# Sh3_Power.net
KiCad netlist of a schematic drawn in Altium Designer
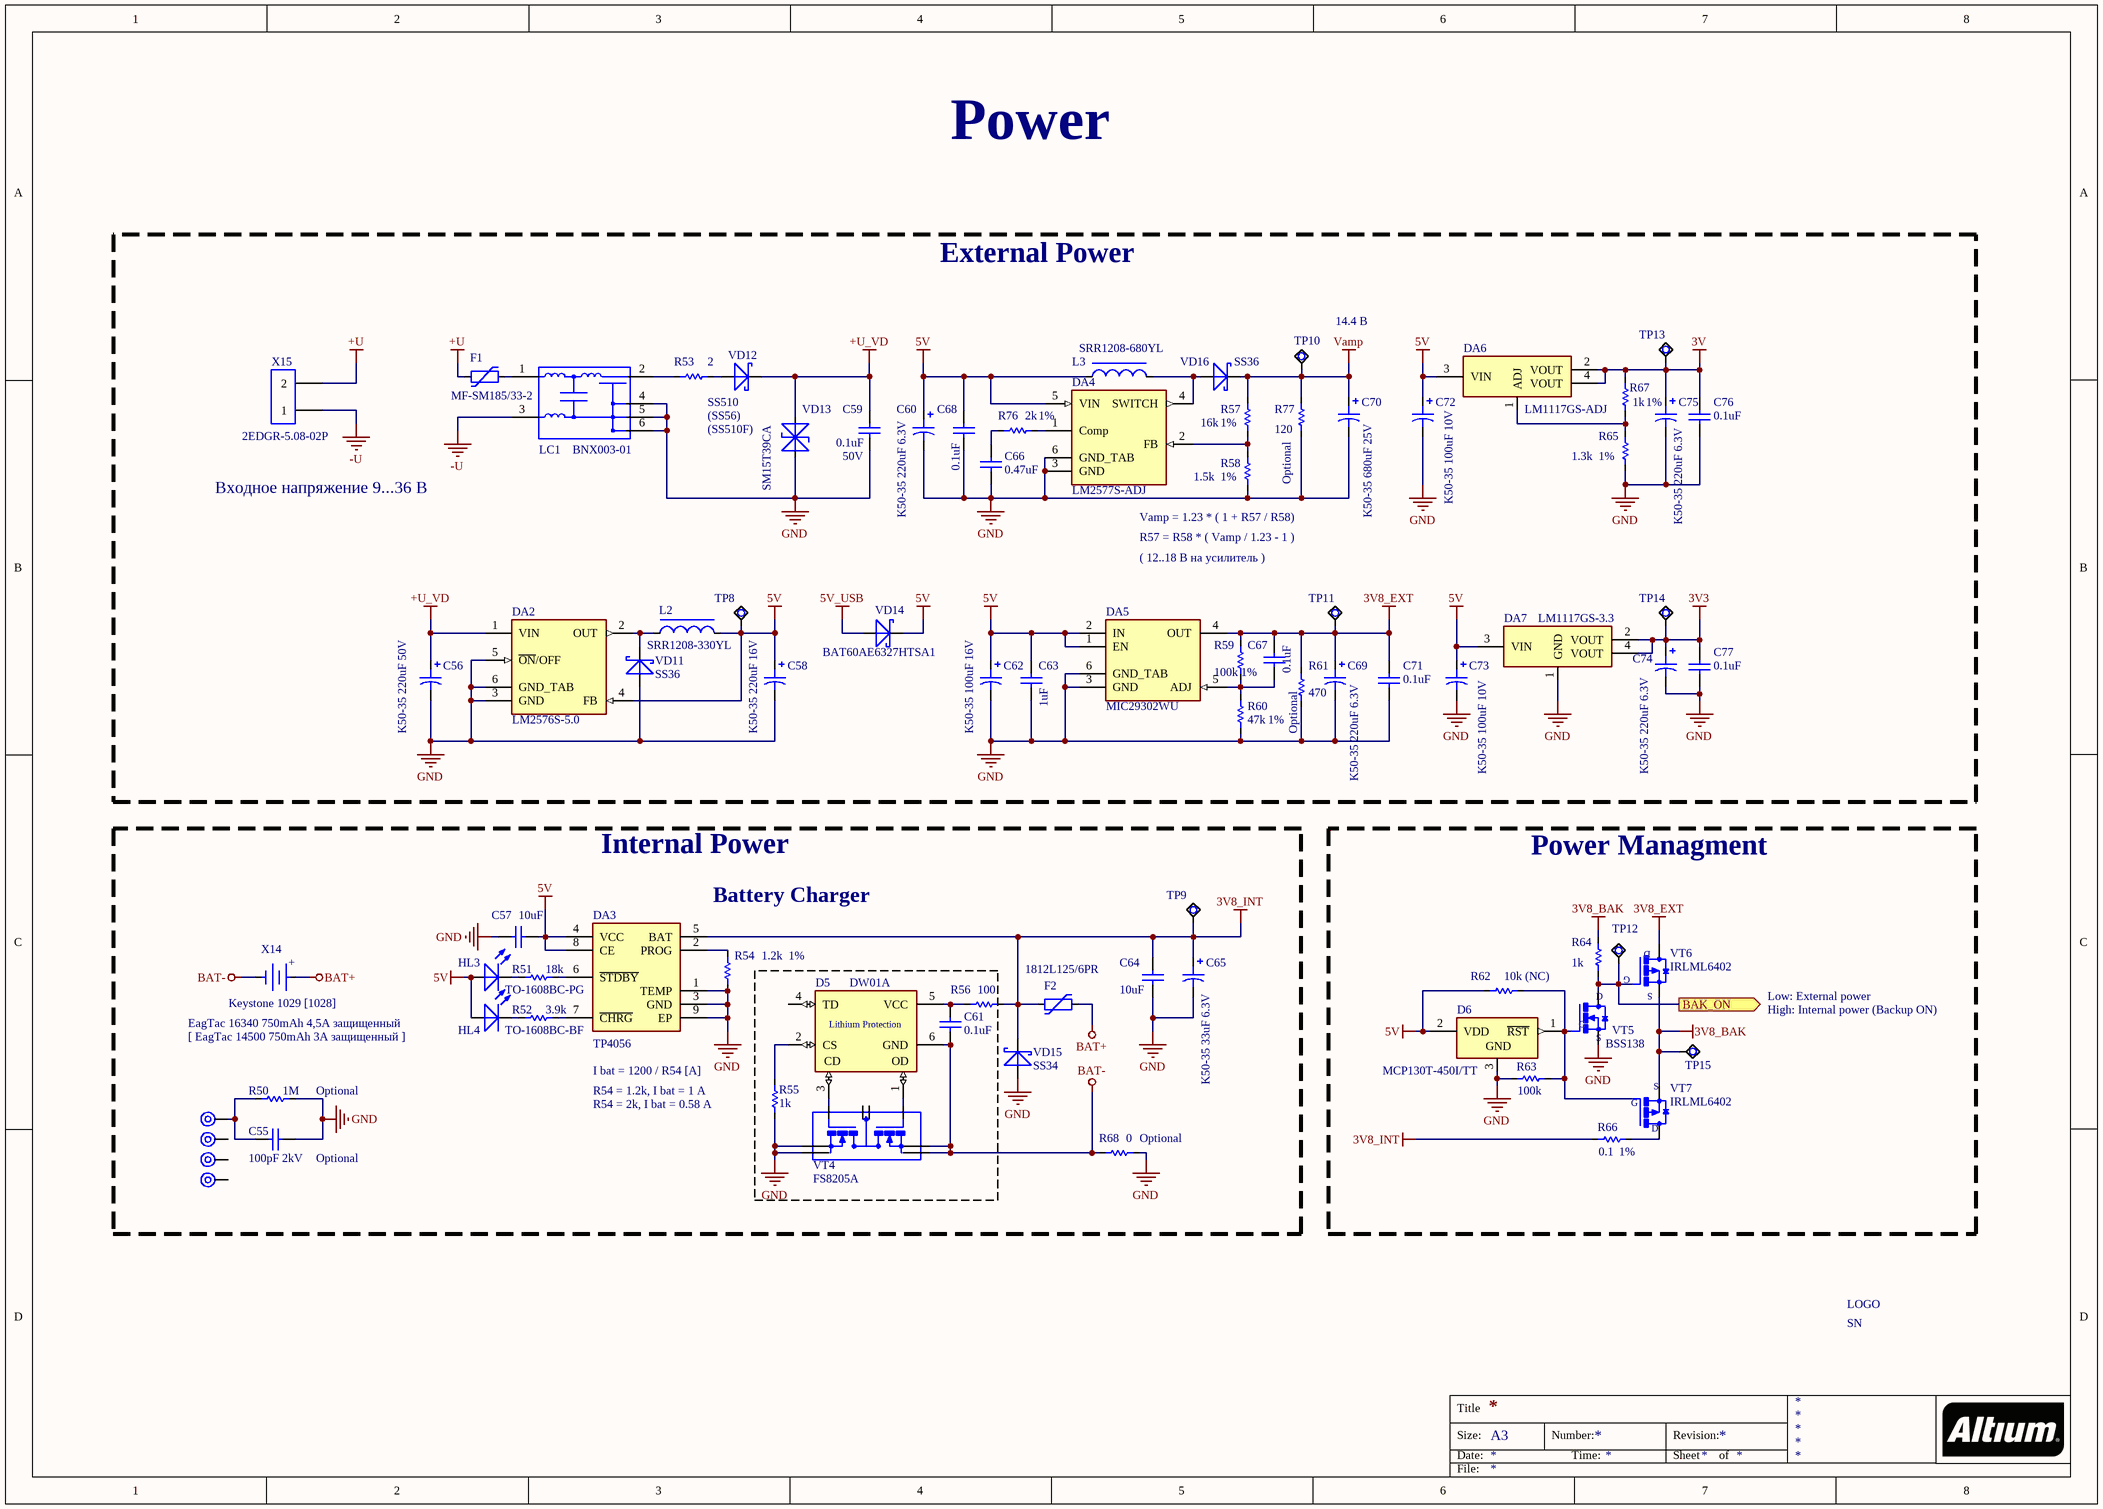
[diagram p0: Sh3_Power.SchDoc]

(export (version "E")
  (design (tool "Eeschema 10.0.6"))
  (components
    (comp (ref "BC1")
      (value "Mounting Hole")
      (footprint "body_connection_1")
      (libsource (lib "MyCompLib") (part "BodyConnector"))
    )
    (comp (ref "BC2")
      (value "Mounting Hole")
      (footprint "body_connection_1")
      (libsource (lib "MyCompLib") (part "BodyConnector"))
    )
    (comp (ref "BC3")
      (value "Mounting Hole")
      (footprint "body_connection_1")
      (libsource (lib "MyCompLib") (part "BodyConnector"))
    )
    (comp (ref "BC4")
      (value "Mounting Hole")
      (footprint "body_connection_1")
      (libsource (lib "MyCompLib") (part "BodyConnector"))
    )
    (comp (ref "C55")
      (value "100pF 2kV")
      (footprint "C_SMD1206")
      (description "C1206C101KGRACAUTO (CC1206JKNPODBN101)")
      (libsource (lib "MyCompLib") (part "C_SMD"))
    )
    (comp (ref "C56")
      (value "K50-35 220uF 50V")
      (footprint "K50-35 10x12.5x5")
      (description "SH050M0220B5S-1012 ECAP 10*12\r\nКонденсатор электролитический алюминиевый")
      (libsource (lib "MyCompLib") (part "K50-35"))
    )
    (comp (ref "C57")
      (value "10uF")
      (footprint "C_SMD0603")
      (description "GRM188R61E106M")
      (libsource (lib "MyCompLib") (part "C_SMD"))
    )
    (comp (ref "C58")
      (value "K50-35 220uF 16V")
      (footprint "K50-35 6.3x11x2.5")
      (description "ECA1CM221 6.3x11 P:2,5мм Конденсатор электролитический алюминиевый")
      (libsource (lib "MyCompLib") (part "K50-35"))
    )
    (comp (ref "C59")
      (value "0.1uF")
      (footprint "C_SMD0603")
      (description "GRM188R71H104KA93D")
      (libsource (lib "MyCompLib") (part "C_SMD"))
    )
    (comp (ref "C60")
      (value "K50-35 220uF 6.3V")
      (footprint "K50-35 6.3x11x2.5")
      (description "ECA0JHG221 5x11мм Р:2,5мм Конденсатор электролитический алюминиевый")
      (libsource (lib "MyCompLib") (part "K50-35"))
    )
    (comp (ref "C61")
      (value "0.1uF")
      (footprint "C_SMD0603")
      (description "GRM188R71H104KA93D")
      (libsource (lib "MyCompLib") (part "C_SMD"))
    )
    (comp (ref "C62")
      (value "K50-35 100uF 16V")
      (footprint "K50-35 6.3x11x2.5")
      (description "SH016M0100A2F-0511 5x11мм Конденсатор электролитический алюминиевый")
      (libsource (lib "MyCompLib") (part "K50-35"))
    )
    (comp (ref "C63")
      (value "1uF")
      (footprint "C_SMD0603")
      (description "GRM188R71E105KA12D")
      (libsource (lib "MyCompLib") (part "C_SMD"))
    )
    (comp (ref "C64")
      (value "10uF")
      (footprint "C_SMD0603")
      (description "GRM188R61E106M")
      (libsource (lib "MyCompLib") (part "C_SMD"))
    )
    (comp (ref "C65")
      (value "K50-35 33uF 6.3V")
      (footprint "K50-35mini 4x7x2")
      (description "Конденсатор электролитический алюминиевый 33 мкФ, 6.3 В, 4х7мм")
      (libsource (lib "MyCompLib") (part "K50-35"))
    )
    (comp (ref "C66")
      (value "0.47uF")
      (footprint "C_SMD0603")
      (description "C1608X7R1H474K080AC")
      (libsource (lib "MyCompLib") (part "C_SMD"))
    )
    (comp (ref "C67")
      (value "0.1uF")
      (footprint "C_SMD0603")
      (description "GRM188R71H104KA93D")
      (libsource (lib "MyCompLib") (part "C_SMD"))
    )
    (comp (ref "C68")
      (value "0.1uF")
      (footprint "C_SMD0603")
      (description "GRM188R71H104KA93D")
      (libsource (lib "MyCompLib") (part "C_SMD"))
    )
    (comp (ref "C69")
      (value "K50-35 220uF 6.3V")
      (footprint "K50-35 6.3x11x2.5")
      (description "ECA0JHG221 5x11мм Р:2,5мм Конденсатор электролитический алюминиевый")
      (libsource (lib "MyCompLib") (part "K50-35"))
    )
    (comp (ref "C70")
      (value "K50-35 680uF 25V")
      (footprint "K50-35 10x12.5x5")
      (description "Конденсатор электролитический алюминиевый 680мкФ, 25В, 10х16мм Р:5мм")
      (libsource (lib "MyCompLib") (part "K50-35"))
    )
    (comp (ref "C71")
      (value "0.1uF")
      (footprint "C_SMD0603")
      (description "GRM188R71H104KA93D")
      (libsource (lib "MyCompLib") (part "C_SMD"))
    )
    (comp (ref "C72")
      (value "K50-35 100uF 10V")
      (footprint "K50-35 5x11x2")
      (description "Конденсатор электролитический алюминиевый")
      (libsource (lib "MyCompLib") (part "K50-35"))
    )
    (comp (ref "C73")
      (value "K50-35 100uF 10V")
      (footprint "K50-35 5x11x2")
      (description "Конденсатор электролитический алюминиевый")
      (libsource (lib "MyCompLib") (part "K50-35"))
    )
    (comp (ref "C74")
      (value "K50-35 220uF 6.3V")
      (footprint "K50-35 6.3x11x2.5")
      (description "ECA0JHG221 5x11мм Р:2,5мм Конденсатор электролитический алюминиевый")
      (libsource (lib "MyCompLib") (part "K50-35"))
    )
    (comp (ref "C75")
      (value "K50-35 220uF 6.3V")
      (footprint "K50-35 6.3x11x2.5")
      (description "ECA0JHG221 5x11мм Р:2,5мм Конденсатор электролитический алюминиевый")
      (libsource (lib "MyCompLib") (part "K50-35"))
    )
    (comp (ref "C76")
      (value "0.1uF")
      (footprint "C_SMD0603")
      (description "GRM188R71H104KA93D")
      (libsource (lib "MyCompLib") (part "C_SMD"))
    )
    (comp (ref "C77")
      (value "0.1uF")
      (footprint "C_SMD0603")
      (description "GRM188R71H104KA93D")
      (libsource (lib "MyCompLib") (part "C_SMD"))
    )
    (comp (ref "D5")
      (value "DW01A")
      (footprint "SOT23-6-D")
      (description "Pushbutton Switch SPST-NC Standard Panel Mount, Front")
      (fields (field (name "MF") "Fortune Semiconductor"))
      (libsource (lib "MyCompLib") (part "DW01A"))
    )
    (comp (ref "D6")
      (value "MCP130T-450I/TT")
      (footprint "SOT23")
      (description "4.50 V 150 ms Microcontroller Supervisory Circuit - SOT-23-3")
      (fields (field (name "MP") "MCP130T-315I/TT") (field (name "MF") "Microchip"))
      (libsource (lib "MyCompLib") (part "MCP130T-450I/TT"))
    )
    (comp (ref "DA2")
      (value "LM2576S-5.0")
      (footprint "TO263-5 - heatsink")
      (description "Импульсный понижающий регулятор напряжения, 5В, 3А, [TO-263]")
      (libsource (lib "MyCompLib") (part "LM2576S"))
    )
    (comp (ref "DA3")
      (value "TP4056")
      (footprint "SOIC127P600X175-9N")
      (description "Li-lon Battery Charger  1A Standalone Linear with Thermal Regulation in SOP-8")
      (libsource (lib "MyCompLib") (part "TP4056"))
    )
    (comp (ref "DA4")
      (value "LM2577S-ADJ")
      (footprint "TO263-5 - heatsink")
      (description "Преобразователь постоянного тока повышающий 3 А вход 3.5...40В выход 5...60В -40...+125°С")
      (libsource (lib "MyCompLib") (part "LM2577S-ADJ"))
    )
    (comp (ref "DA5")
      (value "MIC29302WU")
      (footprint "TO263-5 - heatsink")
      (libsource (lib "MyCompLib") (part "MIC29302WU"))
    )
    (comp (ref "DA6")
      (value "LM1117GS-ADJ")
      (footprint "SOT223")
      (libsource (lib "MyCompLib") (part "LM1117GS-ADJ"))
    )
    (comp (ref "DA7")
      (value "LM1117GS-3.3")
      (footprint "SOT223")
      (libsource (lib "MyCompLib") (part "LM1117GS-3.3"))
    )
    (comp (ref "F1")
      (value "MF-SM185/33-2")
      (footprint "FUSM8867X300N")
      (libsource (lib "MyCompLib") (part "MF-SM185/33-2"))
    )
    (comp (ref "F2")
      (value "1812L125/6PR")
      (footprint "FUSSC324X455X62L")
      (description "Предохранитель SMD 6 VDC 2.5 A")
      (libsource (lib "MyCompLib") (part "1812L125/6PR"))
    )
    (comp (ref "HL3")
      (value "TO-1608BC-PG")
      (footprint "LED_SMD1608GREEN")
      (description "Vf =3.3V, 20mA, 0603 (HL-PST-1608U51GC)")
      (libsource (lib "MyCompLib") (part "LED_SMD"))
    )
    (comp (ref "HL4")
      (value "TO-1608BC-BF")
      (footprint "LED_SMD1608")
      (description "Vf =3.3V, 20mA, 0603 (HL-PST-1608H203BC)")
      (libsource (lib "MyCompLib") (part "LED_SMD"))
    )
    (comp (ref "L2")
      (value "SRR1208-330YL")
      (footprint "SRR1208")
      (libsource (lib "MyCompLib") (part "SRR1208-330YL"))
    )
    (comp (ref "L3")
      (value "SRR1208-680YL")
      (footprint "SRR1208")
      (libsource (lib "MyCompLib") (part "SRR1208-330YL"))
    )
    (comp (ref "LC1")
      (value "BNX003-01")
      (footprint "Murata_BNX_L12MM5_W11MM5_T13MM0_MFG")
      (description "EMI фильтр индуктивно-емкостной 10A 150VDC 40дБ")
      (libsource (lib "MyCompLib") (part "BNX003-01"))
    )
    (comp (ref "N1")
      (value "Logo")
      (footprint "LOGO_SS - bot")
      (description "Print on PCB mask")
      (libsource (lib "MyCompLib") (part "Logo"))
    )
    (comp (ref "N2")
      (value "SN")
      (footprint "KZTA_SN")
      (description "Board Serial Number Placement")
      (libsource (lib "MyCompLib") (part "SerialNumber"))
    )
    (comp (ref "R50")
      (value "1M")
      (footprint "R_SMD1206")
      (description "RC1206JR-071ML")
      (libsource (lib "MyCompLib") (part "R_SMD"))
    )
    (comp (ref "R51")
      (value "18k")
      (footprint "R_SMD0603")
      (description "RC0603FR-0718KL")
      (libsource (lib "MyCompLib") (part "R_SMD"))
    )
    (comp (ref "R52")
      (value "3.9k")
      (footprint "R_SMD0603")
      (description "RC0603FR-073K9L")
      (libsource (lib "MyCompLib") (part "R_SMD"))
    )
    (comp (ref "R53")
      (value "2")
      (footprint "R_SMD4527")
      (description "WSC45272R000FEA SMD чип резистор, с проволочной обмоткой, 4527, 2 Ом, Серия WSC, 2 Вт")
      (libsource (lib "MyCompLib") (part "WSC45272R000FEA"))
    )
    (comp (ref "R54")
      (value "1.2k")
      (footprint "R_SMD0603")
      (description "RC0603FR-071K2L")
      (libsource (lib "MyCompLib") (part "R_SMD"))
    )
    (comp (ref "R55")
      (value "1k")
      (footprint "R_SMD0603")
      (description "RC0603FR-071KL")
      (libsource (lib "MyCompLib") (part "R_SMD"))
    )
    (comp (ref "R56")
      (value "100")
      (footprint "R_SMD0603")
      (description "RC0603FR-07100RL")
      (libsource (lib "MyCompLib") (part "R_SMD"))
    )
    (comp (ref "R57")
      (value "16k")
      (footprint "R_SMD0603")
      (description "RC0603FR-0716KL")
      (libsource (lib "MyCompLib") (part "R_SMD"))
    )
    (comp (ref "R58")
      (value "1.5k")
      (footprint "R_SMD0603")
      (description "RC0603FR-071K5L")
      (libsource (lib "MyCompLib") (part "R_SMD"))
    )
    (comp (ref "R59")
      (value "100k")
      (footprint "R_SMD0603")
      (description "RC0603FR-07100KL")
      (libsource (lib "MyCompLib") (part "R_SMD"))
    )
    (comp (ref "R60")
      (value "47k")
      (footprint "R_SMD0603")
      (description "RC0603FR-0747KL")
      (libsource (lib "MyCompLib") (part "R_SMD"))
    )
    (comp (ref "R61")
      (value "470")
      (footprint "R_SMD0805")
      (description "RC0805FR-07470RL")
      (libsource (lib "MyCompLib") (part "R_SMD"))
    )
    (comp (ref "R62")
      (value "10k (NC)")
      (footprint "R_SMD0603")
      (description "RC0603FR-0710KL (CRCW060310K0FKEA)")
      (libsource (lib "MyCompLib") (part "R_SMD"))
    )
    (comp (ref "R63")
      (value "100k")
      (footprint "R_SMD0603")
      (description "RC0603FR-07100KL")
      (libsource (lib "MyCompLib") (part "R_SMD"))
    )
    (comp (ref "R64")
      (value "1k")
      (footprint "R_SMD0603")
      (description "RC0603FR-071KL")
      (libsource (lib "MyCompLib") (part "R_SMD"))
    )
    (comp (ref "R65")
      (value "1.3k")
      (footprint "R_SMD0603")
      (description "RC0603FR-071K3L")
      (libsource (lib "MyCompLib") (part "R_SMD"))
    )
    (comp (ref "R66")
      (value "0.1")
      (footprint "R_SMD0805")
      (description "RL0805FR-070R1L")
      (libsource (lib "MyCompLib") (part "R_SMD"))
    )
    (comp (ref "R67")
      (value "1k")
      (footprint "R_SMD0603")
      (description "RC0603FR-071KL")
      (libsource (lib "MyCompLib") (part "R_SMD"))
    )
    (comp (ref "R68")
      (value "0")
      (footprint "R_SMD0805")
      (description "RC0805JR-070RL")
      (libsource (lib "MyCompLib") (part "R_SMD"))
    )
    (comp (ref "R76")
      (value "2k")
      (footprint "R_SMD0603")
      (description "RC0603FR-072KL")
      (libsource (lib "MyCompLib") (part "R_SMD"))
    )
    (comp (ref "R77")
      (value "120")
      (footprint "R_SMD0805")
      (description "RC0805FR-07120RL")
      (libsource (lib "MyCompLib") (part "R_SMD"))
    )
    (comp (ref "TP8")
      (value "Test_point")
      (footprint "TEST_POINT")
      (description "Test point for PCB")
      (libsource (lib "MyCompLib") (part "Test_point"))
    )
    (comp (ref "TP9")
      (value "Test_point")
      (footprint "TEST_POINT")
      (description "Test point for PCB")
      (libsource (lib "MyCompLib") (part "Test_point"))
    )
    (comp (ref "TP10")
      (value "Test_point")
      (footprint "TEST_POINT")
      (description "Test point for PCB")
      (libsource (lib "MyCompLib") (part "Test_point"))
    )
    (comp (ref "TP11")
      (value "Test_point")
      (footprint "TEST_POINT")
      (description "Test point for PCB")
      (libsource (lib "MyCompLib") (part "Test_point"))
    )
    (comp (ref "TP12")
      (value "Test_point")
      (footprint "TEST_POINT")
      (description "Test point for PCB")
      (libsource (lib "MyCompLib") (part "Test_point"))
    )
    (comp (ref "TP13")
      (value "Test_point")
      (footprint "TEST_POINT")
      (description "Test point for PCB")
      (libsource (lib "MyCompLib") (part "Test_point"))
    )
    (comp (ref "TP14")
      (value "Test_point")
      (footprint "TEST_POINT")
      (description "Test point for PCB")
      (libsource (lib "MyCompLib") (part "Test_point"))
    )
    (comp (ref "TP15")
      (value "Test_point")
      (footprint "TEST_POINT")
      (description "Test point for PCB")
      (libsource (lib "MyCompLib") (part "Test_point"))
    )
    (comp (ref "VD11")
      (value "SS36")
      (footprint "DO214AB SMC")
      (description "Schottky; DO-214AB; 3.0A IF; 0.75V; 60V; 100A IFRM; 10000V/us; 1000pF")
      (libsource (lib "MyCompLib") (part "SS36"))
    )
    (comp (ref "VD12")
      (value "SS510")
      (footprint "SMC + SMAF")
      (description "Диод Шоттки 5A 100V (SMC)")
      (libsource (lib "MyCompLib") (part "SS510"))
    )
    (comp (ref "VD13")
      (value "SM15T39CA")
      (footprint "DO214AB SMC")
      (description "TVS Diode Bi-Directional SM15T39CA 69.7V, 1500W, SMC 2-Pin")
      (libsource (lib "MyCompLib") (part "SM15T39CA"))
    )
    (comp (ref "VD14")
      (value "BAT60AE6327HTSA1")
      (footprint "SOD-323")
      (description "Диод Шоттки 3А 10В [SOD-323]")
      (libsource (lib "MyCompLib") (part "BAT60AE6327HTSA1"))
    )
    (comp (ref "VD15")
      (value "SS34")
      (footprint "DO214AB SMC")
      (description "Schottky; DO-214AB; 3.0A IF; 0.75V; 40V; 100A IFRM; 10000V/us; 1000pF")
      (libsource (lib "MyCompLib") (part "SS34"))
    )
    (comp (ref "VD16")
      (value "SS36")
      (footprint "DO214AB SMC")
      (description "Schottky; DO-214AB; 3.0A IF; 0.75V; 60V; 100A IFRM; 10000V/us; 1000pF")
      (libsource (lib "MyCompLib") (part "SS36"))
    )
    (comp (ref "VT4")
      (value "FS8205A")
      (footprint "SOP65P640X120-8N")
      (description "20V 6A DUAL N-Channel MOSFET Transistor")
      (libsource (lib "MyCompLib") (part "FS8205A"))
    )
    (comp (ref "VT5")
      (value "BSS138")
      (footprint "SOT23")
      (description "MOSFET, N-канал, 0.2А, 50В, [SOT-23]")
      (libsource (lib "MyCompLib") (part "BSS138"))
    )
    (comp (ref "VT6")
      (value "IRLML6402")
      (footprint "SOT23")
      (description "P-Channel 20V 3.7A _Ta_ 1.3W _Ta_ Surface Mount/SOT-23")
      (fields (field (name "MF") "Infineon Technologies"))
      (libsource (lib "") (part "IRLML6402_1"))
    )
    (comp (ref "VT7")
      (value "IRLML6402")
      (footprint "SOT23")
      (description "P-Channel 20V 3.7A _Ta_ 1.3W _Ta_ Surface Mount/SOT-23")
      (fields (field (name "MF") "Infineon Technologies"))
      (libsource (lib "MyCompLib") (part "IRLML6402"))
    )
    (comp (ref "X14")
      (value "Keystone 1029 [1028]")
      (footprint "BAT_keystone1028+1029")
      (description "16340 2/3A [14500 AA] Battery Holder")
      (libsource (lib "MyCompLib") (part "Combo Battery Holder"))
    )
    (comp (ref "X15")
      (value "2EDGR-5.08-02P")
      (footprint "2EDGR-5.08-02P")
      (libsource (lib "MyCompLib") (part "2EDGR-5.08-02P"))
    )
  )
  (nets
    (net (code "1") (name "+U") (class "Default")
      (node (ref "F1") (pin "1") (pinfunction "1_1") (pintype "passive"))
      (node (ref "X15") (pin "2") (pinfunction "2_2") (pintype "passive"))
    )
    (net (code "2") (name "+U_VD") (class "Default")
      (node (ref "C56") (pin "1") (pinfunction "1_1") (pintype "passive"))
      (node (ref "C59") (pin "1") (pinfunction "1_1") (pintype "passive"))
      (node (ref "DA2") (pin "1") (pinfunction "VIN_1") (pintype "power_in"))
      (node (ref "VD12") (pin "C") (pinfunction "NEG_C") (pintype "passive"))
      (node (ref "VD13") (pin "2") (pinfunction "K_2") (pintype "passive"))
    )
    (net (code "3") (name "-U") (class "Default")
      (node (ref "LC1") (pin "3") (pinfunction "PSG_3") (pintype "passive"))
      (node (ref "X15") (pin "1") (pinfunction "1_1") (pintype "passive"))
    )
    (net (code "4") (name "/BAK_ON") (class "Default")
      (node (ref "R64") (pin "2") (pinfunction "CW_2") (pintype "passive"))
      (node (ref "TP12") (pin "1") (pinfunction "1_1") (pintype "passive"))
      (node (ref "VT5") (pin "3") (pinfunction "D_3") (pintype "passive"))
      (node (ref "VT6") (pin "1") (pinfunction "G_1") (pintype "passive"))
    )
    (net (code "5") (name "3V") (class "Default")
      (node (ref "C75") (pin "1") (pinfunction "1_1") (pintype "passive"))
      (node (ref "C76") (pin "1") (pinfunction "1_1") (pintype "passive"))
      (node (ref "DA6") (pin "2") (pinfunction "VOUT_2") (pintype "power_in"))
      (node (ref "DA6") (pin "4") (pinfunction "VOUT_4") (pintype "power_in"))
      (node (ref "R67") (pin "2") (pinfunction "CW_2") (pintype "passive"))
      (node (ref "TP13") (pin "1") (pinfunction "1_1") (pintype "passive"))
    )
    (net (code "6") (name "3V3") (class "Default")
      (node (ref "C74") (pin "1") (pinfunction "1_1") (pintype "passive"))
      (node (ref "C77") (pin "1") (pinfunction "1_1") (pintype "passive"))
      (node (ref "DA7") (pin "2") (pinfunction "VOUT_2") (pintype "power_in"))
      (node (ref "DA7") (pin "4") (pinfunction "VOUT_4") (pintype "power_in"))
      (node (ref "TP14") (pin "1") (pinfunction "1_1") (pintype "passive"))
    )
    (net (code "7") (name "3V8_BAK") (class "Default")
      (node (ref "R64") (pin "1") (pinfunction "CCW_1") (pintype "passive"))
      (node (ref "TP15") (pin "1") (pinfunction "1_1") (pintype "passive"))
      (node (ref "VT6") (pin "2") (pinfunction "S_2") (pintype "passive"))
      (node (ref "VT7") (pin "2") (pinfunction "S_2") (pintype "passive"))
    )
    (net (code "8") (name "3V8_EXT") (class "Default")
      (node (ref "C67") (pin "1") (pinfunction "1_1") (pintype "passive"))
      (node (ref "C69") (pin "1") (pinfunction "1_1") (pintype "passive"))
      (node (ref "C71") (pin "1") (pinfunction "1_1") (pintype "passive"))
      (node (ref "DA5") (pin "4") (pinfunction "OUT_4") (pintype "power_in"))
      (node (ref "R59") (pin "2") (pinfunction "CW_2") (pintype "passive"))
      (node (ref "R61") (pin "2") (pinfunction "CW_2") (pintype "passive"))
      (node (ref "TP11") (pin "1") (pinfunction "1_1") (pintype "passive"))
      (node (ref "VT6") (pin "3") (pinfunction "D_3") (pintype "passive"))
    )
    (net (code "9") (name "3V8_INT") (class "Default")
      (node (ref "C64") (pin "1") (pinfunction "1_1") (pintype "passive"))
      (node (ref "C65") (pin "1") (pinfunction "1_1") (pintype "passive"))
      (node (ref "DA3") (pin "5") (pinfunction "BAT_5") (pintype "passive"))
      (node (ref "F2") (pin "1") (pinfunction "1_1") (pintype "passive"))
      (node (ref "R56") (pin "1") (pinfunction "CCW_1") (pintype "passive"))
      (node (ref "R66") (pin "2") (pinfunction "CW_2") (pintype "passive"))
      (node (ref "TP9") (pin "1") (pinfunction "1_1") (pintype "passive"))
      (node (ref "VD15") (pin "2") (pinfunction "NEG_2") (pintype "passive"))
    )
    (net (code "10") (name "5V") (class "Default")
      (node (ref "C57") (pin "2") (pinfunction "2_2") (pintype "passive"))
      (node (ref "C58") (pin "1") (pinfunction "1_1") (pintype "passive"))
      (node (ref "C60") (pin "1") (pinfunction "1_1") (pintype "passive"))
      (node (ref "C62") (pin "1") (pinfunction "1_1") (pintype "passive"))
      (node (ref "C63") (pin "1") (pinfunction "1_1") (pintype "passive"))
      (node (ref "C68") (pin "1") (pinfunction "1_1") (pintype "passive"))
      (node (ref "C72") (pin "1") (pinfunction "1_1") (pintype "passive"))
      (node (ref "C73") (pin "1") (pinfunction "1_1") (pintype "passive"))
      (node (ref "D6") (pin "2") (pinfunction "VDD_2") (pintype "power_in"))
      (node (ref "DA2") (pin "4") (pinfunction "FB_4") (pintype "input"))
      (node (ref "DA3") (pin "4") (pinfunction "VCC_4") (pintype "passive"))
      (node (ref "DA3") (pin "8") (pinfunction "CE_8") (pintype "passive"))
      (node (ref "DA4") (pin "5") (pinfunction "VIN_5") (pintype "input"))
      (node (ref "DA5") (pin "1") (pinfunction "EN_1") (pintype "power_in"))
      (node (ref "DA5") (pin "2") (pinfunction "IN_2") (pintype "power_in"))
      (node (ref "DA6") (pin "3") (pinfunction "VIN_3") (pintype "power_in"))
      (node (ref "DA7") (pin "3") (pinfunction "VIN_3") (pintype "power_in"))
      (node (ref "HL3") (pin "1") (pinfunction "POS_1") (pintype "passive"))
      (node (ref "HL4") (pin "1") (pinfunction "POS_1") (pintype "passive"))
      (node (ref "L2") (pin "2") (pinfunction "2_2") (pintype "passive"))
      (node (ref "L3") (pin "1") (pinfunction "1_1") (pintype "passive"))
      (node (ref "R62") (pin "2") (pinfunction "CW_2") (pintype "passive"))
      (node (ref "TP8") (pin "1") (pinfunction "1_1") (pintype "passive"))
      (node (ref "VD14") (pin "2") (pinfunction "NEG_2") (pintype "passive"))
    )
    (net (code "11") (name "5V_USB") (class "Default")
      (node (ref "VD14") (pin "1") (pinfunction "POS_1") (pintype "passive"))
    )
    (net (code "12") (name "BAT+") (class "Default")
      (node (ref "F2") (pin "2") (pinfunction "2_2") (pintype "passive"))
      (node (ref "X14") (pin "POS") (pinfunction "POS_POS") (pintype "passive"))
    )
    (net (code "13") (name "BAT-") (class "Default")
      (node (ref "C61") (pin "2") (pinfunction "2_2") (pintype "passive"))
      (node (ref "D5") (pin "6") (pinfunction "GND_6") (pintype "power_in"))
      (node (ref "R68") (pin "1") (pinfunction "CCW_1") (pintype "passive"))
      (node (ref "VT4") (pin "2") (pinfunction "S1_1_2") (pintype "passive"))
      (node (ref "VT4") (pin "3") (pinfunction "S1_2_3") (pintype "passive"))
      (node (ref "X14") (pin "NEG") (pinfunction "NEG_NEG") (pintype "passive"))
    )
    (net (code "14") (name "GND") (class "Default")
      (node (ref "C55") (pin "2") (pinfunction "2_2") (pintype "passive"))
      (node (ref "C56") (pin "2") (pinfunction "2_2") (pintype "passive"))
      (node (ref "C57") (pin "1") (pinfunction "1_1") (pintype "passive"))
      (node (ref "C58") (pin "2") (pinfunction "2_2") (pintype "passive"))
      (node (ref "C59") (pin "2") (pinfunction "2_2") (pintype "passive"))
      (node (ref "C60") (pin "2") (pinfunction "2_2") (pintype "passive"))
      (node (ref "C62") (pin "2") (pinfunction "2_2") (pintype "passive"))
      (node (ref "C63") (pin "2") (pinfunction "2_2") (pintype "passive"))
      (node (ref "C64") (pin "2") (pinfunction "2_2") (pintype "passive"))
      (node (ref "C65") (pin "2") (pinfunction "2_2") (pintype "passive"))
      (node (ref "C66") (pin "2") (pinfunction "2_2") (pintype "passive"))
      (node (ref "C68") (pin "2") (pinfunction "2_2") (pintype "passive"))
      (node (ref "C69") (pin "2") (pinfunction "2_2") (pintype "passive"))
      (node (ref "C70") (pin "2") (pinfunction "2_2") (pintype "passive"))
      (node (ref "C71") (pin "2") (pinfunction "2_2") (pintype "passive"))
      (node (ref "C72") (pin "2") (pinfunction "2_2") (pintype "passive"))
      (node (ref "C73") (pin "2") (pinfunction "2_2") (pintype "passive"))
      (node (ref "C74") (pin "2") (pinfunction "2_2") (pintype "passive"))
      (node (ref "C75") (pin "2") (pinfunction "2_2") (pintype "passive"))
      (node (ref "C76") (pin "2") (pinfunction "2_2") (pintype "passive"))
      (node (ref "C77") (pin "2") (pinfunction "2_2") (pintype "passive"))
      (node (ref "D6") (pin "3") (pinfunction "VSS_3") (pintype "power_in"))
      (node (ref "DA2") (pin "3") (pinfunction "GND_3") (pintype "passive"))
      (node (ref "DA2") (pin "5") (pinfunction "~{ON}/OFF_5") (pintype "input"))
      (node (ref "DA2") (pin "6") (pinfunction "GND_TAB_6") (pintype "passive"))
      (node (ref "DA3") (pin "1") (pinfunction "TEMP_1") (pintype "passive"))
      (node (ref "DA3") (pin "3") (pinfunction "GND_3") (pintype "passive"))
      (node (ref "DA3") (pin "9") (pinfunction "EP_9") (pintype "passive"))
      (node (ref "DA4") (pin "3") (pinfunction "GND_3") (pintype "passive"))
      (node (ref "DA4") (pin "6") (pinfunction "GND_TAB_6") (pintype "passive"))
      (node (ref "DA5") (pin "3") (pinfunction "GND_3") (pintype "passive"))
      (node (ref "DA5") (pin "6") (pinfunction "GND_TAB_6") (pintype "passive"))
      (node (ref "DA7") (pin "1") (pinfunction "GND_1") (pintype "passive"))
      (node (ref "LC1") (pin "4") (pinfunction "CG_4") (pintype "passive"))
      (node (ref "LC1") (pin "5") (pinfunction "CG_5") (pintype "passive"))
      (node (ref "LC1") (pin "6") (pinfunction "CG_6") (pintype "passive"))
      (node (ref "R50") (pin "2") (pinfunction "CW_2") (pintype "passive"))
      (node (ref "R54") (pin "1") (pinfunction "CCW_1") (pintype "passive"))
      (node (ref "R55") (pin "2") (pinfunction "CW_2") (pintype "passive"))
      (node (ref "R58") (pin "1") (pinfunction "CCW_1") (pintype "passive"))
      (node (ref "R60") (pin "1") (pinfunction "CCW_1") (pintype "passive"))
      (node (ref "R61") (pin "1") (pinfunction "CCW_1") (pintype "passive"))
      (node (ref "R63") (pin "2") (pinfunction "CW_2") (pintype "passive"))
      (node (ref "R65") (pin "1") (pinfunction "CCW_1") (pintype "passive"))
      (node (ref "R68") (pin "2") (pinfunction "CW_2") (pintype "passive"))
      (node (ref "R77") (pin "1") (pinfunction "CCW_1") (pintype "passive"))
      (node (ref "VD11") (pin "1") (pinfunction "POS_1") (pintype "passive"))
      (node (ref "VD13") (pin "1") (pinfunction "A_1") (pintype "passive"))
      (node (ref "VD15") (pin "1") (pinfunction "POS_1") (pintype "passive"))
      (node (ref "VT4") (pin "6") (pinfunction "S2_1_6") (pintype "passive"))
      (node (ref "VT4") (pin "7") (pinfunction "S2_2_7") (pintype "passive"))
      (node (ref "VT5") (pin "2") (pinfunction "S_2") (pintype "passive"))
    )
    (net (code "15") (name "Net-(D5-CS)") (class "Default")
      (node (ref "D5") (pin "2") (pinfunction "CS_2") (pintype "bidirectional"))
      (node (ref "R55") (pin "1") (pinfunction "CCW_1") (pintype "passive"))
    )
    (net (code "16") (name "Net-(D5-OC)") (class "Default")
      (node (ref "D5") (pin "3") (pinfunction "OC_3") (pintype "bidirectional"))
      (node (ref "VT4") (pin "5") (pinfunction "G2_5") (pintype "passive"))
    )
    (net (code "17") (name "Net-(D5-OD)") (class "Default")
      (node (ref "D5") (pin "1") (pinfunction "OD_1") (pintype "bidirectional"))
      (node (ref "VT4") (pin "4") (pinfunction "G1_4") (pintype "passive"))
    )
    (net (code "18") (name "Net-(D5-VCC)") (class "Default")
      (node (ref "C61") (pin "1") (pinfunction "1_1") (pintype "passive"))
      (node (ref "D5") (pin "5") (pinfunction "VCC_5") (pintype "power_in"))
      (node (ref "R56") (pin "2") (pinfunction "CW_2") (pintype "passive"))
    )
    (net (code "19") (name "Net-(D6-~{RST})") (class "Default")
      (node (ref "D6") (pin "1") (pinfunction "~{RST}_1") (pintype "output"))
      (node (ref "R62") (pin "1") (pinfunction "CCW_1") (pintype "passive"))
      (node (ref "R63") (pin "1") (pinfunction "CCW_1") (pintype "passive"))
      (node (ref "VT5") (pin "1") (pinfunction "G_1") (pintype "passive"))
      (node (ref "VT7") (pin "1") (pinfunction "G_1") (pintype "passive"))
    )
    (net (code "20") (name "Net-(DA2-OUT)") (class "Default")
      (node (ref "DA2") (pin "2") (pinfunction "OUT_2") (pintype "output"))
      (node (ref "L2") (pin "1") (pinfunction "1_1") (pintype "passive"))
      (node (ref "VD11") (pin "2") (pinfunction "NEG_2") (pintype "passive"))
    )
    (net (code "21") (name "Net-(DA3-PROG)") (class "Default")
      (node (ref "DA3") (pin "2") (pinfunction "PROG_2") (pintype "passive"))
      (node (ref "R54") (pin "2") (pinfunction "CW_2") (pintype "passive"))
    )
    (net (code "22") (name "Net-(DA3-~{CHRG})") (class "Default")
      (node (ref "DA3") (pin "7") (pinfunction "~{CHRG}_7") (pintype "passive"))
      (node (ref "R52") (pin "1") (pinfunction "CCW_1") (pintype "passive"))
    )
    (net (code "23") (name "Net-(DA3-~{STDBY})") (class "Default")
      (node (ref "DA3") (pin "6") (pinfunction "~{STDBY}_6") (pintype "passive"))
      (node (ref "R51") (pin "1") (pinfunction "CCW_1") (pintype "passive"))
    )
    (net (code "24") (name "Net-(DA4-Comp)") (class "Default")
      (node (ref "DA4") (pin "1") (pinfunction "Comp_1") (pintype "power_in"))
      (node (ref "R76") (pin "1") (pinfunction "CCW_1") (pintype "passive"))
    )
    (net (code "25") (name "Net-(DA4-FB)") (class "Default")
      (node (ref "DA4") (pin "2") (pinfunction "FB_2") (pintype "input"))
      (node (ref "R57") (pin "1") (pinfunction "CCW_1") (pintype "passive"))
      (node (ref "R58") (pin "2") (pinfunction "CW_2") (pintype "passive"))
    )
    (net (code "26") (name "Net-(DA4-SWITCH)") (class "Default")
      (node (ref "DA4") (pin "4") (pinfunction "SWITCH_4") (pintype "output"))
      (node (ref "L3") (pin "2") (pinfunction "2_2") (pintype "passive"))
      (node (ref "VD16") (pin "1") (pinfunction "POS_1") (pintype "passive"))
    )
    (net (code "27") (name "Net-(DA5-ADJ)") (class "Default")
      (node (ref "C67") (pin "2") (pinfunction "2_2") (pintype "passive"))
      (node (ref "DA5") (pin "5") (pinfunction "ADJ_5") (pintype "input"))
      (node (ref "R59") (pin "1") (pinfunction "CCW_1") (pintype "passive"))
      (node (ref "R60") (pin "2") (pinfunction "CW_2") (pintype "passive"))
    )
    (net (code "28") (name "Net-(DA6-ADJ)") (class "Default")
      (node (ref "DA6") (pin "1") (pinfunction "ADJ_1") (pintype "passive"))
      (node (ref "R65") (pin "2") (pinfunction "CW_2") (pintype "passive"))
      (node (ref "R67") (pin "1") (pinfunction "CCW_1") (pintype "passive"))
    )
    (net (code "29") (name "Net-(HL3-NEG)") (class "Default")
      (node (ref "HL3") (pin "2") (pinfunction "NEG_2") (pintype "passive"))
      (node (ref "R51") (pin "2") (pinfunction "CW_2") (pintype "passive"))
    )
    (net (code "30") (name "Net-(HL4-NEG)") (class "Default")
      (node (ref "HL4") (pin "2") (pinfunction "NEG_2") (pintype "passive"))
      (node (ref "R52") (pin "2") (pinfunction "CW_2") (pintype "passive"))
    )
    (net (code "31") (name "Net-(LC1-B)") (class "Default")
      (node (ref "F1") (pin "2") (pinfunction "2_2") (pintype "passive"))
      (node (ref "LC1") (pin "1") (pinfunction "B_1") (pintype "passive"))
    )
    (net (code "32") (name "Net-(LC1-CB)") (class "Default")
      (node (ref "LC1") (pin "2") (pinfunction "CB_2") (pintype "passive"))
      (node (ref "R53") (pin "1") (pinfunction "CCW_1") (pintype "passive"))
    )
    (net (code "33") (name "Net-(R50-CCW)") (class "Default")
      (node (ref "BC1") (pin "1") (pinfunction "1_1") (pintype "passive"))
      (node (ref "C55") (pin "1") (pinfunction "1_1") (pintype "passive"))
      (node (ref "R50") (pin "1") (pinfunction "CCW_1") (pintype "passive"))
    )
    (net (code "34") (name "Net-(R53-CW)") (class "Default")
      (node (ref "R53") (pin "2") (pinfunction "CW_2") (pintype "passive"))
      (node (ref "VD12") (pin "A") (pinfunction "POS_A") (pintype "passive"))
    )
    (net (code "35") (name "Net-(R66-CCW)") (class "Default")
      (node (ref "R66") (pin "1") (pinfunction "CCW_1") (pintype "passive"))
      (node (ref "VT7") (pin "3") (pinfunction "D_3") (pintype "passive"))
    )
    (net (code "36") (name "Net-(R76-CW)") (class "Default")
      (node (ref "C66") (pin "1") (pinfunction "1_1") (pintype "passive"))
      (node (ref "R76") (pin "2") (pinfunction "CW_2") (pintype "passive"))
    )
    (net (code "37") (name "Vamp") (class "Default")
      (node (ref "C70") (pin "1") (pinfunction "1_1") (pintype "passive"))
      (node (ref "R57") (pin "2") (pinfunction "CW_2") (pintype "passive"))
      (node (ref "R77") (pin "2") (pinfunction "CW_2") (pintype "passive"))
      (node (ref "TP10") (pin "1") (pinfunction "1_1") (pintype "passive"))
      (node (ref "VD16") (pin "2") (pinfunction "NEG_2") (pintype "passive"))
    )
    (net (code "38") (name "unconnected-(BC2-Pad1)") (class "Default")
      (node (ref "BC2") (pin "1") (pinfunction "1_1") (pintype "passive"))
    )
    (net (code "39") (name "unconnected-(BC3-Pad1)") (class "Default")
      (node (ref "BC3") (pin "1") (pinfunction "1_1") (pintype "passive"))
    )
    (net (code "40") (name "unconnected-(BC4-Pad1)") (class "Default")
      (node (ref "BC4") (pin "1") (pinfunction "1_1") (pintype "passive"))
    )
    (net (code "41") (name "unconnected-(D5-TD-Pad4)") (class "Default")
      (node (ref "D5") (pin "4") (pinfunction "TD_4") (pintype "bidirectional"))
    )
    (net (code "42") (name "unconnected-(VT4-D12_1-Pad1)") (class "Default")
      (node (ref "VT4") (pin "1") (pinfunction "D12_1_1") (pintype "passive"))
    )
    (net (code "43") (name "unconnected-(VT4-D12_2-Pad8)") (class "Default")
      (node (ref "VT4") (pin "8") (pinfunction "D12_2_8") (pintype "passive"))
    )
  )
)
